# Power.net
KiCad netlist of a schematic drawn in EAGLE
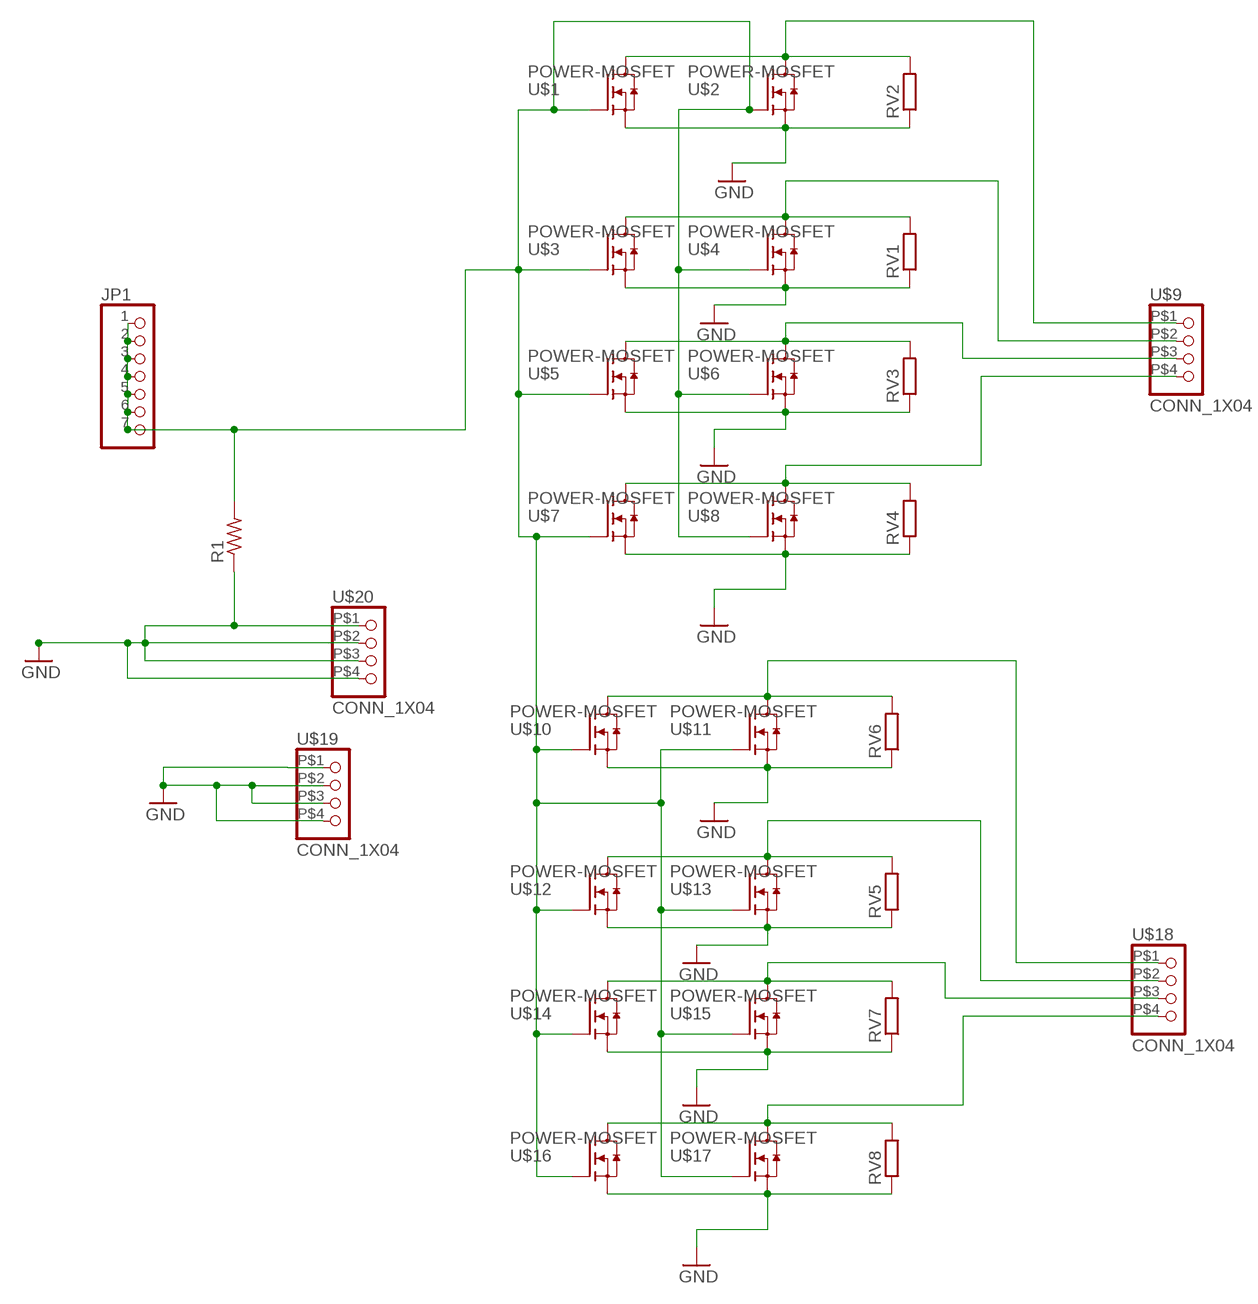
[diagram p0: schematic, sheet 1]

(export (version "E")
  (design (tool "Eeschema 10.0.6"))
  (components
    (comp (ref "JP1")
      (value "PINHD-1X7")
      (footprint "eagle-import:1X07")
      (libsource (lib "eagle-import") (part "PINHD-1X7"))
    )
    (comp (ref "R1")
      (value "R-US_R0603")
      (footprint "eagle-import:R0603")
      (libsource (lib "eagle-import") (part "R-US_R0603"))
    )
    (comp (ref "RV1")
      (value "R-EU_R1210")
      (footprint "eagle-import:R1210")
      (libsource (lib "eagle-import") (part "R-EU_R1210"))
    )
    (comp (ref "RV2")
      (value "R-EU_R1210")
      (footprint "eagle-import:R1210")
      (libsource (lib "eagle-import") (part "R-EU_R1210"))
    )
    (comp (ref "RV3")
      (value "R-EU_R1210")
      (footprint "eagle-import:R1210")
      (libsource (lib "eagle-import") (part "R-EU_R1210"))
    )
    (comp (ref "RV4")
      (value "R-EU_R1210")
      (footprint "eagle-import:R1210")
      (libsource (lib "eagle-import") (part "R-EU_R1210"))
    )
    (comp (ref "RV5")
      (value "R-EU_R1210")
      (footprint "eagle-import:R1210")
      (libsource (lib "eagle-import") (part "R-EU_R1210"))
    )
    (comp (ref "RV6")
      (value "R-EU_R1210")
      (footprint "eagle-import:R1210")
      (libsource (lib "eagle-import") (part "R-EU_R1210"))
    )
    (comp (ref "RV7")
      (value "R-EU_R1210")
      (footprint "eagle-import:R1210")
      (libsource (lib "eagle-import") (part "R-EU_R1210"))
    )
    (comp (ref "RV8")
      (value "R-EU_R1210")
      (footprint "eagle-import:R1210")
      (libsource (lib "eagle-import") (part "R-EU_R1210"))
    )
    (comp (ref "U$1")
      (value "POWER-MOSFET")
      (footprint "eagle-import:BSC010N04LS")
      (libsource (lib "eagle-import") (part "POWER-MOSFET"))
    )
    (comp (ref "U$2")
      (value "POWER-MOSFET")
      (footprint "eagle-import:BSC010N04LS")
      (libsource (lib "eagle-import") (part "POWER-MOSFET"))
    )
    (comp (ref "U$3")
      (value "POWER-MOSFET")
      (footprint "eagle-import:BSC010N04LS")
      (libsource (lib "eagle-import") (part "POWER-MOSFET"))
    )
    (comp (ref "U$4")
      (value "POWER-MOSFET")
      (footprint "eagle-import:BSC010N04LS")
      (libsource (lib "eagle-import") (part "POWER-MOSFET"))
    )
    (comp (ref "U$5")
      (value "POWER-MOSFET")
      (footprint "eagle-import:BSC010N04LS")
      (libsource (lib "eagle-import") (part "POWER-MOSFET"))
    )
    (comp (ref "U$6")
      (value "POWER-MOSFET")
      (footprint "eagle-import:BSC010N04LS")
      (libsource (lib "eagle-import") (part "POWER-MOSFET"))
    )
    (comp (ref "U$7")
      (value "POWER-MOSFET")
      (footprint "eagle-import:BSC010N04LS")
      (libsource (lib "eagle-import") (part "POWER-MOSFET"))
    )
    (comp (ref "U$8")
      (value "POWER-MOSFET")
      (footprint "eagle-import:BSC010N04LS")
      (libsource (lib "eagle-import") (part "POWER-MOSFET"))
    )
    (comp (ref "U$9")
      (value "CONN_1X04")
      (footprint "eagle-import:CONN_1X04")
      (libsource (lib "eagle-import") (part "CONN_1X04"))
    )
    (comp (ref "U$10")
      (value "POWER-MOSFET")
      (footprint "eagle-import:BSC010N04LS")
      (libsource (lib "eagle-import") (part "POWER-MOSFET"))
    )
    (comp (ref "U$11")
      (value "POWER-MOSFET")
      (footprint "eagle-import:BSC010N04LS")
      (libsource (lib "eagle-import") (part "POWER-MOSFET"))
    )
    (comp (ref "U$12")
      (value "POWER-MOSFET")
      (footprint "eagle-import:BSC010N04LS")
      (libsource (lib "eagle-import") (part "POWER-MOSFET"))
    )
    (comp (ref "U$13")
      (value "POWER-MOSFET")
      (footprint "eagle-import:BSC010N04LS")
      (libsource (lib "eagle-import") (part "POWER-MOSFET"))
    )
    (comp (ref "U$14")
      (value "POWER-MOSFET")
      (footprint "eagle-import:BSC010N04LS")
      (libsource (lib "eagle-import") (part "POWER-MOSFET"))
    )
    (comp (ref "U$15")
      (value "POWER-MOSFET")
      (footprint "eagle-import:BSC010N04LS")
      (libsource (lib "eagle-import") (part "POWER-MOSFET"))
    )
    (comp (ref "U$16")
      (value "POWER-MOSFET")
      (footprint "eagle-import:BSC010N04LS")
      (libsource (lib "eagle-import") (part "POWER-MOSFET"))
    )
    (comp (ref "U$17")
      (value "POWER-MOSFET")
      (footprint "eagle-import:BSC010N04LS")
      (libsource (lib "eagle-import") (part "POWER-MOSFET"))
    )
    (comp (ref "U$18")
      (value "CONN_1X04")
      (footprint "eagle-import:CONN_1X04")
      (libsource (lib "eagle-import") (part "CONN_1X04"))
    )
    (comp (ref "U$19")
      (value "CONN_1X04")
      (footprint "eagle-import:CONN_1X04")
      (libsource (lib "eagle-import") (part "CONN_1X04"))
    )
    (comp (ref "U$20")
      (value "CONN_1X04")
      (footprint "eagle-import:CONN_1X04")
      (libsource (lib "eagle-import") (part "CONN_1X04"))
    )
  )
  (nets
    (net (code "1") (name "GND") (class "Default")
      (node (ref "R1") (pin "1") (pinfunction "1_1") (pintype "passive"))
      (node (ref "RV1") (pin "1") (pinfunction "1_1") (pintype "passive"))
      (node (ref "RV2") (pin "1") (pinfunction "1_1") (pintype "passive"))
      (node (ref "RV3") (pin "1") (pinfunction "1_1") (pintype "passive"))
      (node (ref "RV4") (pin "1") (pinfunction "1_1") (pintype "passive"))
      (node (ref "RV5") (pin "1") (pinfunction "1_1") (pintype "passive"))
      (node (ref "RV6") (pin "1") (pinfunction "1_1") (pintype "passive"))
      (node (ref "RV7") (pin "1") (pinfunction "1_1") (pintype "passive"))
      (node (ref "RV8") (pin "1") (pinfunction "1_1") (pintype "passive"))
      (node (ref "U$1") (pin "P$3") (pinfunction "S_P$3") (pintype "passive"))
      (node (ref "U$1") (pin "S") (pinfunction "S_S") (pintype "passive"))
      (node (ref "U$10") (pin "P$3") (pinfunction "S_P$3") (pintype "passive"))
      (node (ref "U$10") (pin "S") (pinfunction "S_S") (pintype "passive"))
      (node (ref "U$11") (pin "P$3") (pinfunction "S_P$3") (pintype "passive"))
      (node (ref "U$11") (pin "S") (pinfunction "S_S") (pintype "passive"))
      (node (ref "U$12") (pin "P$3") (pinfunction "S_P$3") (pintype "passive"))
      (node (ref "U$12") (pin "S") (pinfunction "S_S") (pintype "passive"))
      (node (ref "U$13") (pin "P$3") (pinfunction "S_P$3") (pintype "passive"))
      (node (ref "U$13") (pin "S") (pinfunction "S_S") (pintype "passive"))
      (node (ref "U$14") (pin "P$3") (pinfunction "S_P$3") (pintype "passive"))
      (node (ref "U$14") (pin "S") (pinfunction "S_S") (pintype "passive"))
      (node (ref "U$15") (pin "P$3") (pinfunction "S_P$3") (pintype "passive"))
      (node (ref "U$15") (pin "S") (pinfunction "S_S") (pintype "passive"))
      (node (ref "U$16") (pin "P$3") (pinfunction "S_P$3") (pintype "passive"))
      (node (ref "U$16") (pin "S") (pinfunction "S_S") (pintype "passive"))
      (node (ref "U$17") (pin "P$3") (pinfunction "S_P$3") (pintype "passive"))
      (node (ref "U$17") (pin "S") (pinfunction "S_S") (pintype "passive"))
      (node (ref "U$19") (pin "P$1") (pinfunction "1_P$1") (pintype "passive"))
      (node (ref "U$19") (pin "P$2") (pinfunction "2_P$2") (pintype "passive"))
      (node (ref "U$19") (pin "P$3") (pinfunction "3_P$3") (pintype "passive"))
      (node (ref "U$19") (pin "P$4") (pinfunction "4_P$4") (pintype "passive"))
      (node (ref "U$2") (pin "P$3") (pinfunction "S_P$3") (pintype "passive"))
      (node (ref "U$2") (pin "S") (pinfunction "S_S") (pintype "passive"))
      (node (ref "U$20") (pin "P$1") (pinfunction "1_P$1") (pintype "passive"))
      (node (ref "U$20") (pin "P$2") (pinfunction "2_P$2") (pintype "passive"))
      (node (ref "U$20") (pin "P$3") (pinfunction "3_P$3") (pintype "passive"))
      (node (ref "U$20") (pin "P$4") (pinfunction "4_P$4") (pintype "passive"))
      (node (ref "U$3") (pin "P$3") (pinfunction "S_P$3") (pintype "passive"))
      (node (ref "U$3") (pin "S") (pinfunction "S_S") (pintype "passive"))
      (node (ref "U$4") (pin "P$3") (pinfunction "S_P$3") (pintype "passive"))
      (node (ref "U$4") (pin "S") (pinfunction "S_S") (pintype "passive"))
      (node (ref "U$5") (pin "P$3") (pinfunction "S_P$3") (pintype "passive"))
      (node (ref "U$5") (pin "S") (pinfunction "S_S") (pintype "passive"))
      (node (ref "U$6") (pin "P$3") (pinfunction "S_P$3") (pintype "passive"))
      (node (ref "U$6") (pin "S") (pinfunction "S_S") (pintype "passive"))
      (node (ref "U$7") (pin "P$3") (pinfunction "S_P$3") (pintype "passive"))
      (node (ref "U$7") (pin "S") (pinfunction "S_S") (pintype "passive"))
      (node (ref "U$8") (pin "P$3") (pinfunction "S_P$3") (pintype "passive"))
      (node (ref "U$8") (pin "S") (pinfunction "S_S") (pintype "passive"))
    )
    (net (code "2") (name "Net-(JP1-Pad1)") (class "Default")
      (node (ref "JP1") (pin "1") (pinfunction "1_1") (pintype "passive"))
      (node (ref "JP1") (pin "2") (pinfunction "2_2") (pintype "passive"))
      (node (ref "JP1") (pin "3") (pinfunction "3_3") (pintype "passive"))
      (node (ref "JP1") (pin "4") (pinfunction "4_4") (pintype "passive"))
      (node (ref "JP1") (pin "5") (pinfunction "5_5") (pintype "passive"))
      (node (ref "JP1") (pin "6") (pinfunction "6_6") (pintype "passive"))
      (node (ref "JP1") (pin "7") (pinfunction "7_7") (pintype "passive"))
      (node (ref "R1") (pin "2") (pinfunction "2_2") (pintype "passive"))
      (node (ref "U$1") (pin "G") (pinfunction "G_G") (pintype "passive"))
      (node (ref "U$10") (pin "G") (pinfunction "G_G") (pintype "passive"))
      (node (ref "U$11") (pin "G") (pinfunction "G_G") (pintype "passive"))
      (node (ref "U$12") (pin "G") (pinfunction "G_G") (pintype "passive"))
      (node (ref "U$13") (pin "G") (pinfunction "G_G") (pintype "passive"))
      (node (ref "U$14") (pin "G") (pinfunction "G_G") (pintype "passive"))
      (node (ref "U$15") (pin "G") (pinfunction "G_G") (pintype "passive"))
      (node (ref "U$16") (pin "G") (pinfunction "G_G") (pintype "passive"))
      (node (ref "U$17") (pin "G") (pinfunction "G_G") (pintype "passive"))
      (node (ref "U$2") (pin "G") (pinfunction "G_G") (pintype "passive"))
      (node (ref "U$3") (pin "G") (pinfunction "G_G") (pintype "passive"))
      (node (ref "U$4") (pin "G") (pinfunction "G_G") (pintype "passive"))
      (node (ref "U$5") (pin "G") (pinfunction "G_G") (pintype "passive"))
      (node (ref "U$6") (pin "G") (pinfunction "G_G") (pintype "passive"))
      (node (ref "U$7") (pin "G") (pinfunction "G_G") (pintype "passive"))
      (node (ref "U$8") (pin "G") (pinfunction "G_G") (pintype "passive"))
    )
    (net (code "3") (name "Net-(U$9-1)") (class "Default")
      (node (ref "RV2") (pin "2") (pinfunction "2_2") (pintype "passive"))
      (node (ref "U$1") (pin "D") (pinfunction "D_D") (pintype "passive"))
      (node (ref "U$1") (pin "P$1") (pinfunction "D_P$1") (pintype "passive"))
      (node (ref "U$1") (pin "P$2") (pinfunction "D_P$2") (pintype "passive"))
      (node (ref "U$1") (pin "P$4") (pinfunction "D_P$4") (pintype "passive"))
      (node (ref "U$1") (pin "P$5") (pinfunction "D_P$5") (pintype "passive"))
      (node (ref "U$1") (pin "P$6") (pinfunction "D_P$6") (pintype "passive"))
      (node (ref "U$1") (pin "P$7") (pinfunction "D_P$7") (pintype "passive"))
      (node (ref "U$2") (pin "D") (pinfunction "D_D") (pintype "passive"))
      (node (ref "U$2") (pin "P$1") (pinfunction "D_P$1") (pintype "passive"))
      (node (ref "U$2") (pin "P$2") (pinfunction "D_P$2") (pintype "passive"))
      (node (ref "U$2") (pin "P$4") (pinfunction "D_P$4") (pintype "passive"))
      (node (ref "U$2") (pin "P$5") (pinfunction "D_P$5") (pintype "passive"))
      (node (ref "U$2") (pin "P$6") (pinfunction "D_P$6") (pintype "passive"))
      (node (ref "U$2") (pin "P$7") (pinfunction "D_P$7") (pintype "passive"))
      (node (ref "U$9") (pin "P$1") (pinfunction "1_P$1") (pintype "passive"))
    )
    (net (code "4") (name "Net-(U$9-2)") (class "Default")
      (node (ref "RV1") (pin "2") (pinfunction "2_2") (pintype "passive"))
      (node (ref "U$3") (pin "D") (pinfunction "D_D") (pintype "passive"))
      (node (ref "U$3") (pin "P$1") (pinfunction "D_P$1") (pintype "passive"))
      (node (ref "U$3") (pin "P$2") (pinfunction "D_P$2") (pintype "passive"))
      (node (ref "U$3") (pin "P$4") (pinfunction "D_P$4") (pintype "passive"))
      (node (ref "U$3") (pin "P$5") (pinfunction "D_P$5") (pintype "passive"))
      (node (ref "U$3") (pin "P$6") (pinfunction "D_P$6") (pintype "passive"))
      (node (ref "U$3") (pin "P$7") (pinfunction "D_P$7") (pintype "passive"))
      (node (ref "U$4") (pin "D") (pinfunction "D_D") (pintype "passive"))
      (node (ref "U$4") (pin "P$1") (pinfunction "D_P$1") (pintype "passive"))
      (node (ref "U$4") (pin "P$2") (pinfunction "D_P$2") (pintype "passive"))
      (node (ref "U$4") (pin "P$4") (pinfunction "D_P$4") (pintype "passive"))
      (node (ref "U$4") (pin "P$5") (pinfunction "D_P$5") (pintype "passive"))
      (node (ref "U$4") (pin "P$6") (pinfunction "D_P$6") (pintype "passive"))
      (node (ref "U$4") (pin "P$7") (pinfunction "D_P$7") (pintype "passive"))
      (node (ref "U$9") (pin "P$2") (pinfunction "2_P$2") (pintype "passive"))
    )
    (net (code "5") (name "Net-(U$9-3)") (class "Default")
      (node (ref "RV3") (pin "2") (pinfunction "2_2") (pintype "passive"))
      (node (ref "U$5") (pin "D") (pinfunction "D_D") (pintype "passive"))
      (node (ref "U$5") (pin "P$1") (pinfunction "D_P$1") (pintype "passive"))
      (node (ref "U$5") (pin "P$2") (pinfunction "D_P$2") (pintype "passive"))
      (node (ref "U$5") (pin "P$4") (pinfunction "D_P$4") (pintype "passive"))
      (node (ref "U$5") (pin "P$5") (pinfunction "D_P$5") (pintype "passive"))
      (node (ref "U$5") (pin "P$6") (pinfunction "D_P$6") (pintype "passive"))
      (node (ref "U$5") (pin "P$7") (pinfunction "D_P$7") (pintype "passive"))
      (node (ref "U$6") (pin "D") (pinfunction "D_D") (pintype "passive"))
      (node (ref "U$6") (pin "P$1") (pinfunction "D_P$1") (pintype "passive"))
      (node (ref "U$6") (pin "P$2") (pinfunction "D_P$2") (pintype "passive"))
      (node (ref "U$6") (pin "P$4") (pinfunction "D_P$4") (pintype "passive"))
      (node (ref "U$6") (pin "P$5") (pinfunction "D_P$5") (pintype "passive"))
      (node (ref "U$6") (pin "P$6") (pinfunction "D_P$6") (pintype "passive"))
      (node (ref "U$6") (pin "P$7") (pinfunction "D_P$7") (pintype "passive"))
      (node (ref "U$9") (pin "P$3") (pinfunction "3_P$3") (pintype "passive"))
    )
    (net (code "6") (name "Net-(U$9-4)") (class "Default")
      (node (ref "RV4") (pin "2") (pinfunction "2_2") (pintype "passive"))
      (node (ref "U$7") (pin "D") (pinfunction "D_D") (pintype "passive"))
      (node (ref "U$7") (pin "P$1") (pinfunction "D_P$1") (pintype "passive"))
      (node (ref "U$7") (pin "P$2") (pinfunction "D_P$2") (pintype "passive"))
      (node (ref "U$7") (pin "P$4") (pinfunction "D_P$4") (pintype "passive"))
      (node (ref "U$7") (pin "P$5") (pinfunction "D_P$5") (pintype "passive"))
      (node (ref "U$7") (pin "P$6") (pinfunction "D_P$6") (pintype "passive"))
      (node (ref "U$7") (pin "P$7") (pinfunction "D_P$7") (pintype "passive"))
      (node (ref "U$8") (pin "D") (pinfunction "D_D") (pintype "passive"))
      (node (ref "U$8") (pin "P$1") (pinfunction "D_P$1") (pintype "passive"))
      (node (ref "U$8") (pin "P$2") (pinfunction "D_P$2") (pintype "passive"))
      (node (ref "U$8") (pin "P$4") (pinfunction "D_P$4") (pintype "passive"))
      (node (ref "U$8") (pin "P$5") (pinfunction "D_P$5") (pintype "passive"))
      (node (ref "U$8") (pin "P$6") (pinfunction "D_P$6") (pintype "passive"))
      (node (ref "U$8") (pin "P$7") (pinfunction "D_P$7") (pintype "passive"))
      (node (ref "U$9") (pin "P$4") (pinfunction "4_P$4") (pintype "passive"))
    )
    (net (code "7") (name "Net-(U$18-1)") (class "Default")
      (node (ref "RV6") (pin "2") (pinfunction "2_2") (pintype "passive"))
      (node (ref "U$10") (pin "D") (pinfunction "D_D") (pintype "passive"))
      (node (ref "U$10") (pin "P$1") (pinfunction "D_P$1") (pintype "passive"))
      (node (ref "U$10") (pin "P$2") (pinfunction "D_P$2") (pintype "passive"))
      (node (ref "U$10") (pin "P$4") (pinfunction "D_P$4") (pintype "passive"))
      (node (ref "U$10") (pin "P$5") (pinfunction "D_P$5") (pintype "passive"))
      (node (ref "U$10") (pin "P$6") (pinfunction "D_P$6") (pintype "passive"))
      (node (ref "U$10") (pin "P$7") (pinfunction "D_P$7") (pintype "passive"))
      (node (ref "U$11") (pin "D") (pinfunction "D_D") (pintype "passive"))
      (node (ref "U$11") (pin "P$1") (pinfunction "D_P$1") (pintype "passive"))
      (node (ref "U$11") (pin "P$2") (pinfunction "D_P$2") (pintype "passive"))
      (node (ref "U$11") (pin "P$4") (pinfunction "D_P$4") (pintype "passive"))
      (node (ref "U$11") (pin "P$5") (pinfunction "D_P$5") (pintype "passive"))
      (node (ref "U$11") (pin "P$6") (pinfunction "D_P$6") (pintype "passive"))
      (node (ref "U$11") (pin "P$7") (pinfunction "D_P$7") (pintype "passive"))
      (node (ref "U$18") (pin "P$1") (pinfunction "1_P$1") (pintype "passive"))
    )
    (net (code "8") (name "Net-(U$18-2)") (class "Default")
      (node (ref "RV5") (pin "2") (pinfunction "2_2") (pintype "passive"))
      (node (ref "U$12") (pin "D") (pinfunction "D_D") (pintype "passive"))
      (node (ref "U$12") (pin "P$1") (pinfunction "D_P$1") (pintype "passive"))
      (node (ref "U$12") (pin "P$2") (pinfunction "D_P$2") (pintype "passive"))
      (node (ref "U$12") (pin "P$4") (pinfunction "D_P$4") (pintype "passive"))
      (node (ref "U$12") (pin "P$5") (pinfunction "D_P$5") (pintype "passive"))
      (node (ref "U$12") (pin "P$6") (pinfunction "D_P$6") (pintype "passive"))
      (node (ref "U$12") (pin "P$7") (pinfunction "D_P$7") (pintype "passive"))
      (node (ref "U$13") (pin "D") (pinfunction "D_D") (pintype "passive"))
      (node (ref "U$13") (pin "P$1") (pinfunction "D_P$1") (pintype "passive"))
      (node (ref "U$13") (pin "P$2") (pinfunction "D_P$2") (pintype "passive"))
      (node (ref "U$13") (pin "P$4") (pinfunction "D_P$4") (pintype "passive"))
      (node (ref "U$13") (pin "P$5") (pinfunction "D_P$5") (pintype "passive"))
      (node (ref "U$13") (pin "P$6") (pinfunction "D_P$6") (pintype "passive"))
      (node (ref "U$13") (pin "P$7") (pinfunction "D_P$7") (pintype "passive"))
      (node (ref "U$18") (pin "P$2") (pinfunction "2_P$2") (pintype "passive"))
    )
    (net (code "9") (name "Net-(U$18-3)") (class "Default")
      (node (ref "RV7") (pin "2") (pinfunction "2_2") (pintype "passive"))
      (node (ref "U$14") (pin "D") (pinfunction "D_D") (pintype "passive"))
      (node (ref "U$14") (pin "P$1") (pinfunction "D_P$1") (pintype "passive"))
      (node (ref "U$14") (pin "P$2") (pinfunction "D_P$2") (pintype "passive"))
      (node (ref "U$14") (pin "P$4") (pinfunction "D_P$4") (pintype "passive"))
      (node (ref "U$14") (pin "P$5") (pinfunction "D_P$5") (pintype "passive"))
      (node (ref "U$14") (pin "P$6") (pinfunction "D_P$6") (pintype "passive"))
      (node (ref "U$14") (pin "P$7") (pinfunction "D_P$7") (pintype "passive"))
      (node (ref "U$15") (pin "D") (pinfunction "D_D") (pintype "passive"))
      (node (ref "U$15") (pin "P$1") (pinfunction "D_P$1") (pintype "passive"))
      (node (ref "U$15") (pin "P$2") (pinfunction "D_P$2") (pintype "passive"))
      (node (ref "U$15") (pin "P$4") (pinfunction "D_P$4") (pintype "passive"))
      (node (ref "U$15") (pin "P$5") (pinfunction "D_P$5") (pintype "passive"))
      (node (ref "U$15") (pin "P$6") (pinfunction "D_P$6") (pintype "passive"))
      (node (ref "U$15") (pin "P$7") (pinfunction "D_P$7") (pintype "passive"))
      (node (ref "U$18") (pin "P$3") (pinfunction "3_P$3") (pintype "passive"))
    )
    (net (code "10") (name "Net-(U$18-4)") (class "Default")
      (node (ref "RV8") (pin "2") (pinfunction "2_2") (pintype "passive"))
      (node (ref "U$16") (pin "D") (pinfunction "D_D") (pintype "passive"))
      (node (ref "U$16") (pin "P$1") (pinfunction "D_P$1") (pintype "passive"))
      (node (ref "U$16") (pin "P$2") (pinfunction "D_P$2") (pintype "passive"))
      (node (ref "U$16") (pin "P$4") (pinfunction "D_P$4") (pintype "passive"))
      (node (ref "U$16") (pin "P$5") (pinfunction "D_P$5") (pintype "passive"))
      (node (ref "U$16") (pin "P$6") (pinfunction "D_P$6") (pintype "passive"))
      (node (ref "U$16") (pin "P$7") (pinfunction "D_P$7") (pintype "passive"))
      (node (ref "U$17") (pin "D") (pinfunction "D_D") (pintype "passive"))
      (node (ref "U$17") (pin "P$1") (pinfunction "D_P$1") (pintype "passive"))
      (node (ref "U$17") (pin "P$2") (pinfunction "D_P$2") (pintype "passive"))
      (node (ref "U$17") (pin "P$4") (pinfunction "D_P$4") (pintype "passive"))
      (node (ref "U$17") (pin "P$5") (pinfunction "D_P$5") (pintype "passive"))
      (node (ref "U$17") (pin "P$6") (pinfunction "D_P$6") (pintype "passive"))
      (node (ref "U$17") (pin "P$7") (pinfunction "D_P$7") (pintype "passive"))
      (node (ref "U$18") (pin "P$4") (pinfunction "4_P$4") (pintype "passive"))
    )
  )
)
